# FremoLNShield.net
KiCad netlist of a schematic drawn in EAGLE
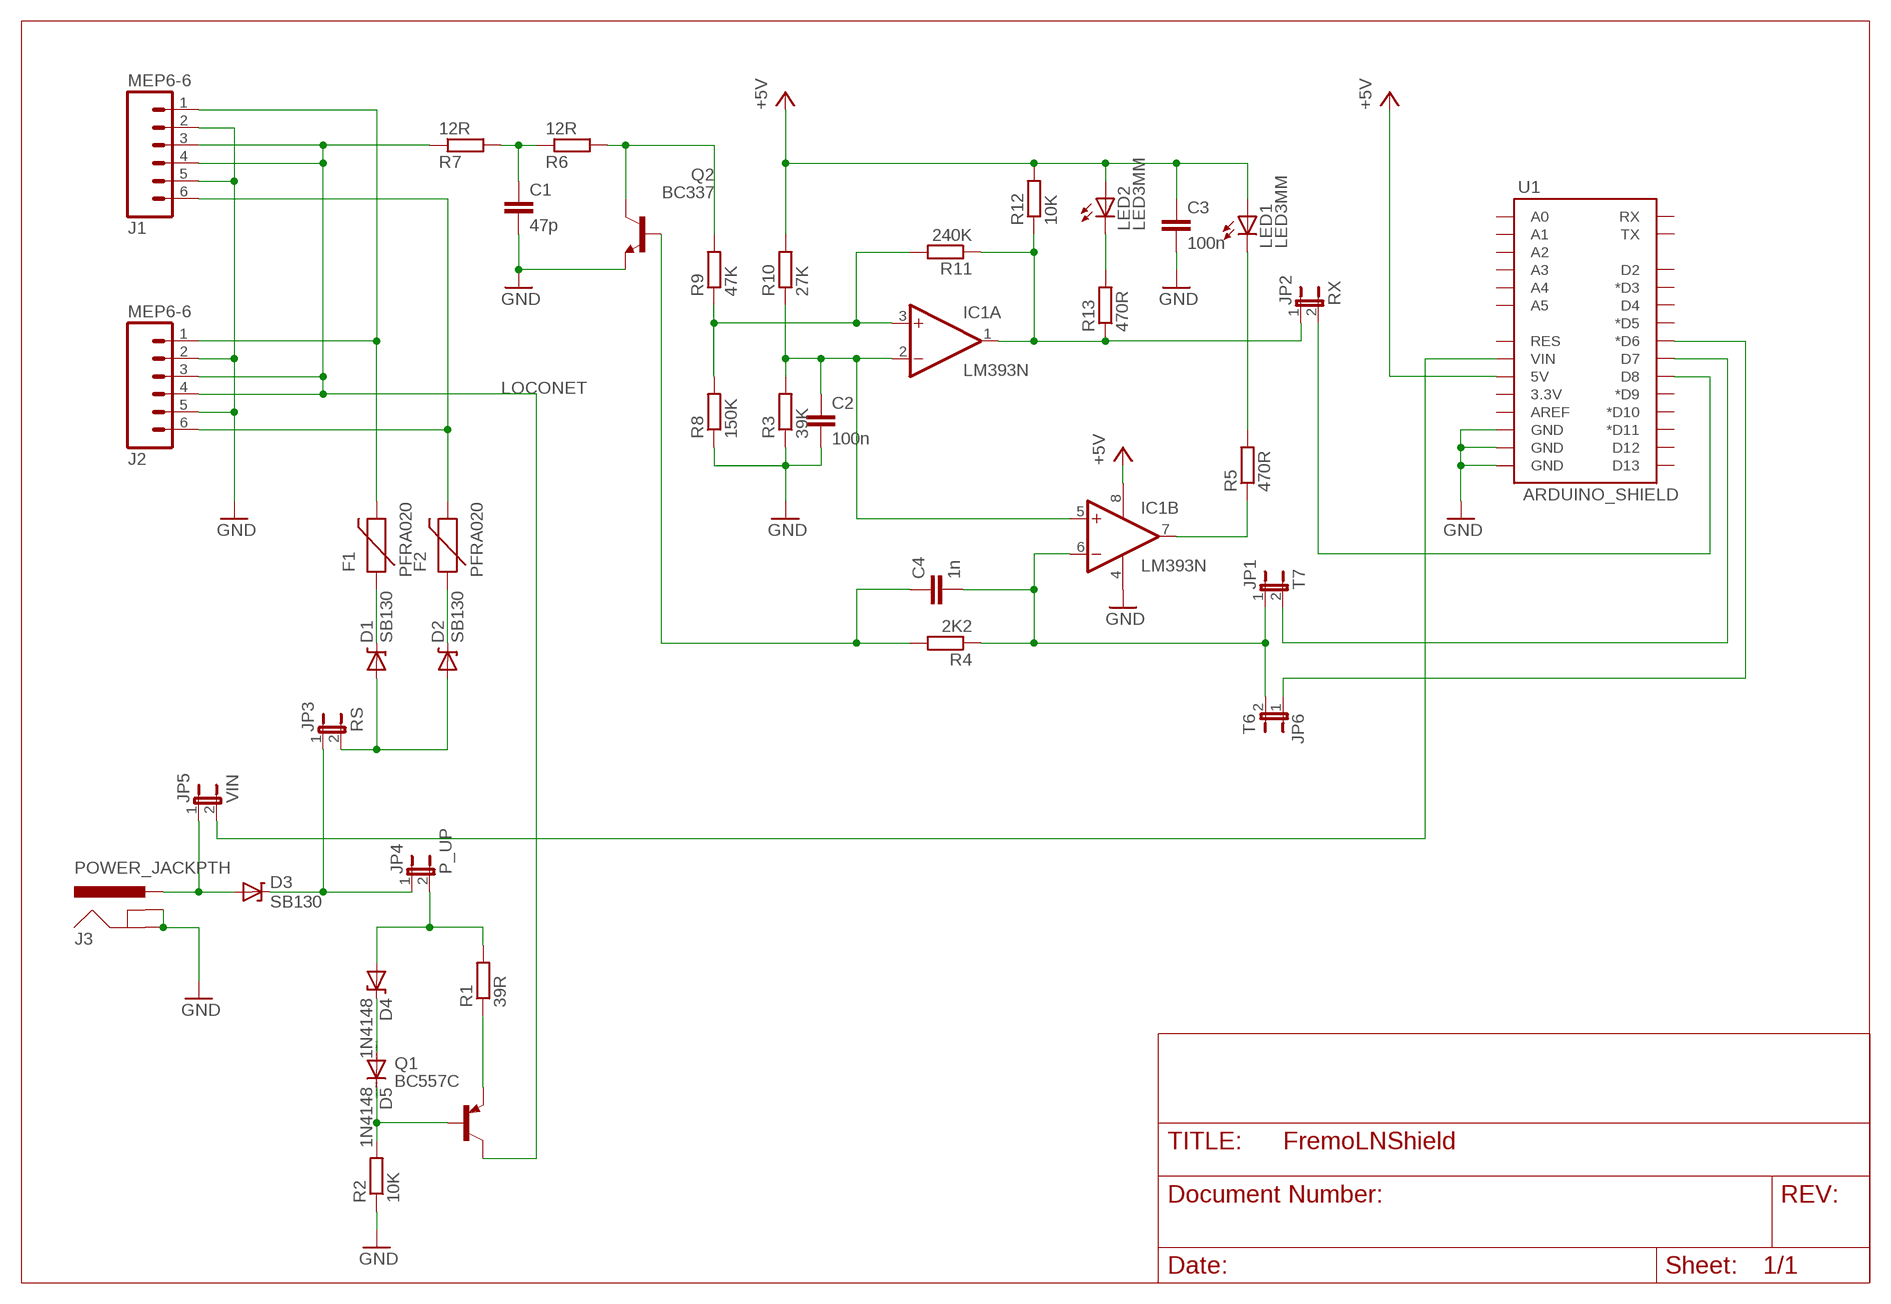
[diagram p0: schematic, sheet 1]

(export (version "E")
  (design (tool "Eeschema 10.0.6"))
  (components
    (comp (ref "C1")
      (value "47p")
      (footprint "eagle-import:C025-025X050")
      (libsource (lib "eagle-import") (part "C-EU025-025X050"))
    )
    (comp (ref "C2")
      (value "100n")
      (footprint "eagle-import:C025-025X050")
      (libsource (lib "eagle-import") (part "C-EU025-025X050"))
    )
    (comp (ref "C3")
      (value "100n")
      (footprint "eagle-import:C025-025X050")
      (libsource (lib "eagle-import") (part "C-EU025-025X050"))
    )
    (comp (ref "C4")
      (value "1n")
      (footprint "eagle-import:C025-025X050")
      (libsource (lib "eagle-import") (part "C-EU025-025X050"))
    )
    (comp (ref "D1")
      (value "SB130")
      (footprint "eagle-import:DIODE-ZENER")
      (libsource (lib "eagle-import") (part "DIODE-ZENERPTH"))
    )
    (comp (ref "D2")
      (value "SB130")
      (footprint "eagle-import:DIODE-ZENER")
      (libsource (lib "eagle-import") (part "DIODE-ZENERPTH"))
    )
    (comp (ref "D3")
      (value "SB130")
      (footprint "eagle-import:DIODE-ZENER")
      (libsource (lib "eagle-import") (part "DIODE-ZENERPTH"))
    )
    (comp (ref "D4")
      (value "1N4148")
      (footprint "eagle-import:DIODE-ZENER")
      (libsource (lib "eagle-import") (part "DIODE-ZENERPTH"))
    )
    (comp (ref "D5")
      (value "1N4148")
      (footprint "eagle-import:DO35-10")
      (libsource (lib "eagle-import") (part "1N4148DO35-10"))
    )
    (comp (ref "F1")
      (value "PFRA020")
      (footprint "eagle-import:PTC")
      (libsource (lib "eagle-import") (part "PTCPTH"))
    )
    (comp (ref "F2")
      (value "PFRA020")
      (footprint "eagle-import:PTC")
      (libsource (lib "eagle-import") (part "PTCPTH"))
    )
    (comp (ref "IC1")
      (value "LM393N")
      (footprint "eagle-import:DIL08")
      (libsource (lib "eagle-import") (part "LM393N"))
    )
    (comp (ref "J1")
      (value "MEP6-6")
      (footprint "eagle-import:RJ11-6")
      (libsource (lib "eagle-import") (part "RJ11-6PTH"))
    )
    (comp (ref "J2")
      (value "MEP6-6")
      (footprint "eagle-import:RJ11-6")
      (libsource (lib "eagle-import") (part "RJ11-6PTH"))
    )
    (comp (ref "J3")
      (value "POWER_JACKPTH")
      (footprint "eagle-import:POWER_JACK_PTH")
      (libsource (lib "eagle-import") (part "POWER_JACKPTH"))
    )
    (comp (ref "JP1")
      (value "T7")
      (footprint "eagle-import:1X02")
      (libsource (lib "eagle-import") (part "JUMPER-2PTH"))
    )
    (comp (ref "JP2")
      (value "RX")
      (footprint "eagle-import:1X02")
      (libsource (lib "eagle-import") (part "JUMPER-2PTH"))
    )
    (comp (ref "JP3")
      (value "RS")
      (footprint "eagle-import:1X02")
      (libsource (lib "eagle-import") (part "JUMPER-2PTH"))
    )
    (comp (ref "JP4")
      (value "P_UP")
      (footprint "eagle-import:1X02")
      (libsource (lib "eagle-import") (part "JUMPER-2PTH"))
    )
    (comp (ref "JP5")
      (value "VIN")
      (footprint "eagle-import:1X02")
      (libsource (lib "eagle-import") (part "JUMPER-2PTH"))
    )
    (comp (ref "JP6")
      (value "T6")
      (footprint "eagle-import:1X02")
      (libsource (lib "eagle-import") (part "JUMPER-2PTH"))
    )
    (comp (ref "LED1")
      (value "LED3MM")
      (footprint "eagle-import:PFEIL3_LED3MM")
      (libsource (lib "eagle-import") (part "PFEIL3_LED3MM"))
    )
    (comp (ref "LED2")
      (value "LED3MM")
      (footprint "eagle-import:PFEIL3_LED3MM")
      (libsource (lib "eagle-import") (part "PFEIL3_LED3MM"))
    )
    (comp (ref "Q1")
      (value "BC557C")
      (footprint "eagle-import:TO92")
      (libsource (lib "eagle-import") (part "BC557"))
    )
    (comp (ref "Q2")
      (value "BC337")
      (footprint "eagle-import:TO92")
      (libsource (lib "eagle-import") (part "BC337"))
    )
    (comp (ref "R1")
      (value "39R")
      (footprint "eagle-import:0207_10")
      (libsource (lib "eagle-import") (part "R-EU_0207/10"))
    )
    (comp (ref "R2")
      (value "10K")
      (footprint "eagle-import:0207_10")
      (libsource (lib "eagle-import") (part "R-EU_0207/10"))
    )
    (comp (ref "R3")
      (value "39K")
      (footprint "eagle-import:0207_10")
      (libsource (lib "eagle-import") (part "R-EU_0207/10"))
    )
    (comp (ref "R4")
      (value "2K2")
      (footprint "eagle-import:0207_10")
      (libsource (lib "eagle-import") (part "R-EU_0207/10"))
    )
    (comp (ref "R5")
      (value "470R")
      (footprint "eagle-import:0207_10")
      (libsource (lib "eagle-import") (part "R-EU_0207/10"))
    )
    (comp (ref "R6")
      (value "12R")
      (footprint "eagle-import:0207_10")
      (libsource (lib "eagle-import") (part "R-EU_0207/10"))
    )
    (comp (ref "R7")
      (value "12R")
      (footprint "eagle-import:0207_10")
      (libsource (lib "eagle-import") (part "R-EU_0207/10"))
    )
    (comp (ref "R8")
      (value "150K")
      (footprint "eagle-import:0207_10")
      (libsource (lib "eagle-import") (part "R-EU_0207/10"))
    )
    (comp (ref "R9")
      (value "47K")
      (footprint "eagle-import:0207_10")
      (libsource (lib "eagle-import") (part "R-EU_0207/10"))
    )
    (comp (ref "R10")
      (value "27K")
      (footprint "eagle-import:0207_10")
      (libsource (lib "eagle-import") (part "R-EU_0207/10"))
    )
    (comp (ref "R11")
      (value "240K")
      (footprint "eagle-import:0207_10")
      (libsource (lib "eagle-import") (part "R-EU_0207/10"))
    )
    (comp (ref "R12")
      (value "10K")
      (footprint "eagle-import:0207_10")
      (libsource (lib "eagle-import") (part "R-EU_0207/10"))
    )
    (comp (ref "R13")
      (value "470R")
      (footprint "eagle-import:0207_10")
      (libsource (lib "eagle-import") (part "R-EU_0207/10"))
    )
    (comp (ref "U1")
      (value "ARDUINO_SHIELD")
      (footprint "eagle-import:DUEMILANOVE_SHIELD")
      (libsource (lib "eagle-import") (part "ARDUINO_SHIELDLABEL"))
    )
  )
  (nets
    (net (code "1") (name "+5V") (class "Default")
      (node (ref "C3") (pin "1") (pinfunction "1_1") (pintype "passive"))
      (node (ref "IC1") (pin "8") (pinfunction "V+_8") (pintype "power_in"))
      (node (ref "LED1") (pin "A") (pinfunction "A_A") (pintype "passive"))
      (node (ref "LED2") (pin "A") (pinfunction "A_A") (pintype "passive"))
      (node (ref "R10") (pin "2") (pinfunction "2_2") (pintype "passive"))
      (node (ref "R12") (pin "2") (pinfunction "2_2") (pintype "passive"))
      (node (ref "U1") (pin "5V") (pinfunction "5V_5V") (pintype "bidirectional"))
    )
    (net (code "2") (name "/LOCONET") (class "Default")
      (node (ref "J1") (pin "3") (pinfunction "3_3") (pintype "passive"))
      (node (ref "J1") (pin "4") (pinfunction "4_4") (pintype "passive"))
      (node (ref "J2") (pin "3") (pinfunction "3_3") (pintype "passive"))
      (node (ref "J2") (pin "4") (pinfunction "4_4") (pintype "passive"))
      (node (ref "Q1") (pin "3") (pinfunction "C_3") (pintype "passive"))
      (node (ref "R7") (pin "1") (pinfunction "1_1") (pintype "passive"))
    )
    (net (code "3") (name "GND") (class "Default")
      (node (ref "C1") (pin "2") (pinfunction "2_2") (pintype "passive"))
      (node (ref "C2") (pin "2") (pinfunction "2_2") (pintype "passive"))
      (node (ref "C3") (pin "2") (pinfunction "2_2") (pintype "passive"))
      (node (ref "IC1") (pin "4") (pinfunction "V-_4") (pintype "power_in"))
      (node (ref "J1") (pin "2") (pinfunction "2_2") (pintype "passive"))
      (node (ref "J1") (pin "5") (pinfunction "5_5") (pintype "passive"))
      (node (ref "J2") (pin "2") (pinfunction "2_2") (pintype "passive"))
      (node (ref "J2") (pin "5") (pinfunction "5_5") (pintype "passive"))
      (node (ref "J3") (pin "GND") (pinfunction "GND_GND") (pintype "bidirectional"))
      (node (ref "J3") (pin "GNDBREAK") (pinfunction "GNDBREAK_GNDBREAK") (pintype "bidirectional"))
      (node (ref "Q2") (pin "1") (pinfunction "E_1") (pintype "passive"))
      (node (ref "R2") (pin "1") (pinfunction "1_1") (pintype "passive"))
      (node (ref "R3") (pin "1") (pinfunction "1_1") (pintype "passive"))
      (node (ref "R8") (pin "1") (pinfunction "1_1") (pintype "passive"))
      (node (ref "U1") (pin "GND@0") (pinfunction "GND_GND@0") (pintype "bidirectional"))
      (node (ref "U1") (pin "GND@1") (pinfunction "GND_GND@1") (pintype "bidirectional"))
      (node (ref "U1") (pin "GND@2") (pinfunction "GND_GND@2") (pintype "bidirectional"))
    )
    (net (code "4") (name "Net-(C1-Pad1)") (class "Default")
      (node (ref "C1") (pin "1") (pinfunction "1_1") (pintype "passive"))
      (node (ref "R6") (pin "1") (pinfunction "1_1") (pintype "passive"))
      (node (ref "R7") (pin "2") (pinfunction "2_2") (pintype "passive"))
    )
    (net (code "5") (name "Net-(D1-A)") (class "Default")
      (node (ref "D1") (pin "P$2") (pinfunction "A_P$2") (pintype "passive"))
      (node (ref "D2") (pin "P$2") (pinfunction "A_P$2") (pintype "passive"))
      (node (ref "JP3") (pin "2") (pinfunction "2_2") (pintype "passive"))
    )
    (net (code "6") (name "Net-(D1-C)") (class "Default")
      (node (ref "D1") (pin "P$1") (pinfunction "C_P$1") (pintype "passive"))
      (node (ref "F1") (pin "P$1") (pinfunction "1_P$1") (pintype "bidirectional"))
    )
    (net (code "7") (name "Net-(D2-C)") (class "Default")
      (node (ref "D2") (pin "P$1") (pinfunction "C_P$1") (pintype "passive"))
      (node (ref "F2") (pin "P$1") (pinfunction "1_P$1") (pintype "bidirectional"))
    )
    (net (code "8") (name "Net-(D3-A)") (class "Default")
      (node (ref "D3") (pin "P$2") (pinfunction "A_P$2") (pintype "passive"))
      (node (ref "J3") (pin "PWR") (pinfunction "PWR_PWR") (pintype "bidirectional"))
      (node (ref "JP5") (pin "1") (pinfunction "1_1") (pintype "passive"))
    )
    (net (code "9") (name "Net-(D3-C)") (class "Default")
      (node (ref "D3") (pin "P$1") (pinfunction "C_P$1") (pintype "passive"))
      (node (ref "JP3") (pin "1") (pinfunction "1_1") (pintype "passive"))
      (node (ref "JP4") (pin "1") (pinfunction "1_1") (pintype "passive"))
    )
    (net (code "10") (name "Net-(D4-A)") (class "Default")
      (node (ref "D4") (pin "P$2") (pinfunction "A_P$2") (pintype "passive"))
      (node (ref "JP4") (pin "2") (pinfunction "2_2") (pintype "passive"))
      (node (ref "R1") (pin "2") (pinfunction "2_2") (pintype "passive"))
    )
    (net (code "11") (name "Net-(D4-C)") (class "Default")
      (node (ref "D4") (pin "P$1") (pinfunction "C_P$1") (pintype "passive"))
      (node (ref "D5") (pin "A") (pinfunction "A_A") (pintype "passive"))
    )
    (net (code "12") (name "Net-(F1-2)") (class "Default")
      (node (ref "F1") (pin "P$2") (pinfunction "2_P$2") (pintype "bidirectional"))
      (node (ref "J1") (pin "1") (pinfunction "1_1") (pintype "passive"))
      (node (ref "J2") (pin "1") (pinfunction "1_1") (pintype "passive"))
    )
    (net (code "13") (name "Net-(F2-2)") (class "Default")
      (node (ref "F2") (pin "P$2") (pinfunction "2_P$2") (pintype "bidirectional"))
      (node (ref "J1") (pin "6") (pinfunction "6_6") (pintype "passive"))
      (node (ref "J2") (pin "6") (pinfunction "6_6") (pintype "passive"))
    )
    (net (code "14") (name "Net-(IC1A-+IN)") (class "Default")
      (node (ref "IC1") (pin "3") (pinfunction "+IN_3") (pintype "input"))
      (node (ref "R11") (pin "2") (pinfunction "2_2") (pintype "passive"))
      (node (ref "R8") (pin "2") (pinfunction "2_2") (pintype "passive"))
      (node (ref "R9") (pin "1") (pinfunction "1_1") (pintype "passive"))
    )
    (net (code "15") (name "Net-(IC1A--IN)") (class "Default")
      (node (ref "C2") (pin "1") (pinfunction "1_1") (pintype "passive"))
      (node (ref "IC1") (pin "2") (pinfunction "-IN_2") (pintype "input"))
      (node (ref "IC1") (pin "5") (pinfunction "+IN_5") (pintype "input"))
      (node (ref "R10") (pin "1") (pinfunction "1_1") (pintype "passive"))
      (node (ref "R3") (pin "2") (pinfunction "2_2") (pintype "passive"))
    )
    (net (code "16") (name "Net-(IC1A-OUT)") (class "Default")
      (node (ref "IC1") (pin "1") (pinfunction "OUT_1") (pintype "output"))
      (node (ref "JP2") (pin "1") (pinfunction "1_1") (pintype "passive"))
      (node (ref "R11") (pin "1") (pinfunction "1_1") (pintype "passive"))
      (node (ref "R12") (pin "1") (pinfunction "1_1") (pintype "passive"))
      (node (ref "R13") (pin "1") (pinfunction "1_1") (pintype "passive"))
    )
    (net (code "17") (name "Net-(IC1B--IN)") (class "Default")
      (node (ref "C4") (pin "2") (pinfunction "2_2") (pintype "passive"))
      (node (ref "IC1") (pin "6") (pinfunction "-IN_6") (pintype "input"))
      (node (ref "JP1") (pin "1") (pinfunction "1_1") (pintype "passive"))
      (node (ref "JP6") (pin "2") (pinfunction "2_2") (pintype "passive"))
      (node (ref "R4") (pin "1") (pinfunction "1_1") (pintype "passive"))
    )
    (net (code "18") (name "Net-(IC1B-OUT)") (class "Default")
      (node (ref "IC1") (pin "7") (pinfunction "OUT_7") (pintype "output"))
      (node (ref "R5") (pin "1") (pinfunction "1_1") (pintype "passive"))
    )
    (net (code "19") (name "Net-(JP1-Pad2)") (class "Default")
      (node (ref "JP1") (pin "2") (pinfunction "2_2") (pintype "passive"))
      (node (ref "U1") (pin "D7") (pinfunction "D7_D7") (pintype "bidirectional"))
    )
    (net (code "20") (name "Net-(JP2-Pad2)") (class "Default")
      (node (ref "JP2") (pin "2") (pinfunction "2_2") (pintype "passive"))
      (node (ref "U1") (pin "D8") (pinfunction "D8_D8") (pintype "bidirectional"))
    )
    (net (code "21") (name "Net-(JP5-Pad2)") (class "Default")
      (node (ref "JP5") (pin "2") (pinfunction "2_2") (pintype "passive"))
      (node (ref "U1") (pin "VIN") (pinfunction "VIN_VIN") (pintype "bidirectional"))
    )
    (net (code "22") (name "Net-(LED1-C)") (class "Default")
      (node (ref "LED1") (pin "K") (pinfunction "C_K") (pintype "passive"))
      (node (ref "R5") (pin "2") (pinfunction "2_2") (pintype "passive"))
    )
    (net (code "23") (name "Net-(LED2-C)") (class "Default")
      (node (ref "LED2") (pin "K") (pinfunction "C_K") (pintype "passive"))
      (node (ref "R13") (pin "2") (pinfunction "2_2") (pintype "passive"))
    )
    (net (code "24") (name "Net-(Q1-B)") (class "Default")
      (node (ref "D5") (pin "C") (pinfunction "C_C") (pintype "passive"))
      (node (ref "Q1") (pin "2") (pinfunction "B_2") (pintype "passive"))
      (node (ref "R2") (pin "2") (pinfunction "2_2") (pintype "passive"))
    )
    (net (code "25") (name "Net-(Q1-E)") (class "Default")
      (node (ref "Q1") (pin "1") (pinfunction "E_1") (pintype "passive"))
      (node (ref "R1") (pin "1") (pinfunction "1_1") (pintype "passive"))
    )
    (net (code "26") (name "Net-(Q2-B)") (class "Default")
      (node (ref "C4") (pin "1") (pinfunction "1_1") (pintype "passive"))
      (node (ref "Q2") (pin "2") (pinfunction "B_2") (pintype "passive"))
      (node (ref "R4") (pin "2") (pinfunction "2_2") (pintype "passive"))
    )
    (net (code "27") (name "Net-(Q2-C)") (class "Default")
      (node (ref "Q2") (pin "3") (pinfunction "C_3") (pintype "passive"))
      (node (ref "R6") (pin "2") (pinfunction "2_2") (pintype "passive"))
      (node (ref "R9") (pin "2") (pinfunction "2_2") (pintype "passive"))
    )
    (net (code "28") (name "Net-(U1-*D6)") (class "Default")
      (node (ref "JP6") (pin "1") (pinfunction "1_1") (pintype "passive"))
      (node (ref "U1") (pin "D6") (pinfunction "*D6_D6") (pintype "bidirectional"))
    )
    (net (code "29") (name "unconnected-(U1-*D3-PadD3)") (class "Default")
      (node (ref "U1") (pin "D3") (pinfunction "*D3_D3") (pintype "bidirectional"))
    )
    (net (code "30") (name "unconnected-(U1-*D5-PadD5)") (class "Default")
      (node (ref "U1") (pin "D5") (pinfunction "*D5_D5") (pintype "bidirectional"))
    )
    (net (code "31") (name "unconnected-(U1-*D9-PadD9)") (class "Default")
      (node (ref "U1") (pin "D9") (pinfunction "*D9_D9") (pintype "bidirectional"))
    )
    (net (code "32") (name "unconnected-(U1-*D10-PadD10)") (class "Default")
      (node (ref "U1") (pin "D10") (pinfunction "*D10_D10") (pintype "bidirectional"))
    )
    (net (code "33") (name "unconnected-(U1-*D11-PadD11)") (class "Default")
      (node (ref "U1") (pin "D11") (pinfunction "*D11_D11") (pintype "bidirectional"))
    )
    (net (code "34") (name "unconnected-(U1-Pad3.3V)") (class "Default")
      (node (ref "U1") (pin "3.3V") (pinfunction "3.3V_3.3V") (pintype "bidirectional"))
    )
    (net (code "35") (name "unconnected-(U1-PadA0)") (class "Default")
      (node (ref "U1") (pin "A0") (pinfunction "A0_A0") (pintype "bidirectional"))
    )
    (net (code "36") (name "unconnected-(U1-PadA1)") (class "Default")
      (node (ref "U1") (pin "A1") (pinfunction "A1_A1") (pintype "bidirectional"))
    )
    (net (code "37") (name "unconnected-(U1-PadA2)") (class "Default")
      (node (ref "U1") (pin "A2") (pinfunction "A2_A2") (pintype "bidirectional"))
    )
    (net (code "38") (name "unconnected-(U1-PadA3)") (class "Default")
      (node (ref "U1") (pin "A3") (pinfunction "A3_A3") (pintype "bidirectional"))
    )
    (net (code "39") (name "unconnected-(U1-PadA4)") (class "Default")
      (node (ref "U1") (pin "A4") (pinfunction "A4_A4") (pintype "bidirectional"))
    )
    (net (code "40") (name "unconnected-(U1-PadA5)") (class "Default")
      (node (ref "U1") (pin "A5") (pinfunction "A5_A5") (pintype "bidirectional"))
    )
    (net (code "41") (name "unconnected-(U1-PadAREF)") (class "Default")
      (node (ref "U1") (pin "AREF") (pinfunction "AREF_AREF") (pintype "bidirectional"))
    )
    (net (code "42") (name "unconnected-(U1-PadD2)") (class "Default")
      (node (ref "U1") (pin "D2") (pinfunction "D2_D2") (pintype "bidirectional"))
    )
    (net (code "43") (name "unconnected-(U1-PadD4)") (class "Default")
      (node (ref "U1") (pin "D4") (pinfunction "D4_D4") (pintype "bidirectional"))
    )
    (net (code "44") (name "unconnected-(U1-PadD12)") (class "Default")
      (node (ref "U1") (pin "D12") (pinfunction "D12_D12") (pintype "bidirectional"))
    )
    (net (code "45") (name "unconnected-(U1-PadD13)") (class "Default")
      (node (ref "U1") (pin "D13") (pinfunction "D13_D13") (pintype "bidirectional"))
    )
    (net (code "46") (name "unconnected-(U1-PadRES)") (class "Default")
      (node (ref "U1") (pin "RES") (pinfunction "RES_RES") (pintype "bidirectional"))
    )
    (net (code "47") (name "unconnected-(U1-PadRX)") (class "Default")
      (node (ref "U1") (pin "RX") (pinfunction "RX_RX") (pintype "bidirectional"))
    )
    (net (code "48") (name "unconnected-(U1-PadTX)") (class "Default")
      (node (ref "U1") (pin "TX") (pinfunction "TX_TX") (pintype "bidirectional"))
    )
  )
)
